# pulse.net
KiCad netlist of a schematic drawn in EAGLE
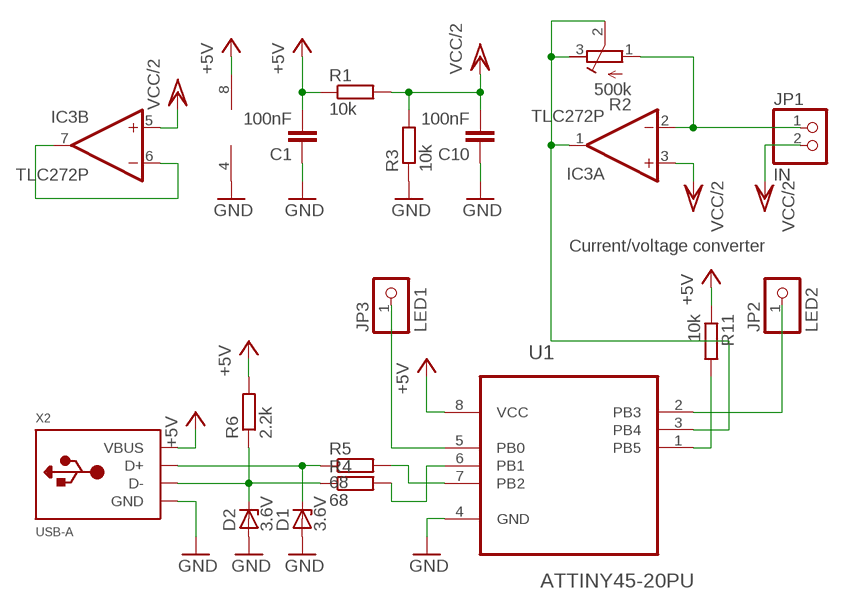
[diagram p0: schematic, sheet 1]

(export (version "E")
  (design (tool "Eeschema 10.0.6"))
  (components
    (comp (ref "C1")
      (value "100nF")
      (footprint "eagle-import:C075-032X103")
      (libsource (lib "eagle-import") (part "C-EU075-032X103"))
    )
    (comp (ref "C10")
      (value "100nF")
      (footprint "eagle-import:C050-025X075")
      (libsource (lib "eagle-import") (part "C-EU050-025X075"))
    )
    (comp (ref "D1")
      (value "3.6V")
      (footprint "eagle-import:ZDIO-2.5")
      (libsource (lib "eagle-import") (part "ZENER-DIODEZD-2.5"))
    )
    (comp (ref "D2")
      (value "3.6V")
      (footprint "eagle-import:ZDIO-5")
      (libsource (lib "eagle-import") (part "ZENER-DIODEZD-5"))
    )
    (comp (ref "IC3")
      (value "TLC272P")
      (footprint "eagle-import:DIL08")
      (libsource (lib "eagle-import") (part "TLC272P"))
    )
    (comp (ref "JP1")
      (value "IN")
      (footprint "eagle-import:1X02")
      (libsource (lib "eagle-import") (part "PINHD-1X2"))
    )
    (comp (ref "JP2")
      (value "LED2")
      (footprint "eagle-import:1X01")
      (libsource (lib "eagle-import") (part "PINHD-1X1"))
    )
    (comp (ref "JP3")
      (value "LED1")
      (footprint "eagle-import:1X01")
      (libsource (lib "eagle-import") (part "PINHD-1X1"))
    )
    (comp (ref "R1")
      (value "10k")
      (footprint "eagle-import:0207_12")
      (libsource (lib "eagle-import") (part "R-EU_0207/12"))
    )
    (comp (ref "R2")
      (value "500k")
      (footprint "eagle-import:RTRIM64W")
      (libsource (lib "eagle-import") (part "R-TRIMM64W"))
    )
    (comp (ref "R3")
      (value "10k")
      (footprint "eagle-import:0204V")
      (libsource (lib "eagle-import") (part "R-EU_0204/2V"))
    )
    (comp (ref "R4")
      (value "68")
      (footprint "eagle-import:0204V")
      (libsource (lib "eagle-import") (part "R-EU_0204/2V"))
    )
    (comp (ref "R5")
      (value "68")
      (footprint "eagle-import:0204V")
      (libsource (lib "eagle-import") (part "R-EU_0204/2V"))
    )
    (comp (ref "R6")
      (value "2.2k")
      (footprint "eagle-import:0204V")
      (libsource (lib "eagle-import") (part "R-EU_0204/2V"))
    )
    (comp (ref "R11")
      (value "10k")
      (footprint "eagle-import:0204_7")
      (libsource (lib "eagle-import") (part "R-EU_0204/7"))
    )
    (comp (ref "U1")
      (value "ATTINY45-20PU")
      (footprint "eagle-import:DIP254P762X533-8")
      (libsource (lib "eagle-import") (part "ATTINY45-20PU"))
    )
    (comp (ref "X2")
      (value "USB-A")
      (footprint "eagle-import:MOLEX_480371000")
      (libsource (lib "eagle-import") (part "USB-A"))
    )
  )
  (nets
    (net (code "1") (name "+5V") (class "Default")
      (node (ref "C1") (pin "2") (pinfunction "2_2") (pintype "passive"))
      (node (ref "IC3") (pin "8") (pinfunction "V+_8") (pintype "power_in"))
      (node (ref "R1") (pin "1") (pinfunction "1_1") (pintype "passive"))
      (node (ref "R11") (pin "1") (pinfunction "1_1") (pintype "passive"))
      (node (ref "R6") (pin "2") (pinfunction "2_2") (pintype "passive"))
      (node (ref "U1") (pin "8") (pinfunction "VCC_8") (pintype "power_in"))
      (node (ref "X2") (pin "1") (pinfunction "VBUS_1") (pintype "power_in"))
    )
    (net (code "2") (name "GND") (class "Default")
      (node (ref "C1") (pin "1") (pinfunction "1_1") (pintype "passive"))
      (node (ref "C10") (pin "1") (pinfunction "1_1") (pintype "passive"))
      (node (ref "D1") (pin "A") (pinfunction "A_A") (pintype "passive"))
      (node (ref "D2") (pin "A") (pinfunction "A_A") (pintype "passive"))
      (node (ref "IC3") (pin "4") (pinfunction "V-_4") (pintype "power_in"))
      (node (ref "R3") (pin "1") (pinfunction "1_1") (pintype "passive"))
      (node (ref "U1") (pin "4") (pinfunction "GND_4") (pintype "passive"))
      (node (ref "X2") (pin "4") (pinfunction "GND_4") (pintype "power_in"))
    )
    (net (code "3") (name "Net-(IC3A--IN)") (class "Default")
      (node (ref "IC3") (pin "2") (pinfunction "-IN_2") (pintype "input"))
      (node (ref "JP1") (pin "1") (pinfunction "1_1") (pintype "passive"))
      (node (ref "R2") (pin "1") (pinfunction "A_1") (pintype "passive"))
    )
    (net (code "4") (name "Net-(IC3A-OUT)") (class "Default")
      (node (ref "IC3") (pin "1") (pinfunction "OUT_1") (pintype "output"))
      (node (ref "R2") (pin "2") (pinfunction "S_2") (pintype "passive"))
      (node (ref "R2") (pin "3") (pinfunction "E_3") (pintype "passive"))
      (node (ref "U1") (pin "3") (pinfunction "PB4_3") (pintype "bidirectional"))
    )
    (net (code "5") (name "Net-(IC3B--IN)") (class "Default")
      (node (ref "IC3") (pin "6") (pinfunction "-IN_6") (pintype "input"))
      (node (ref "IC3") (pin "7") (pinfunction "OUT_7") (pintype "output"))
    )
    (net (code "6") (name "Net-(U1-PB0)") (class "Default")
      (node (ref "JP3") (pin "1") (pinfunction "1_1") (pintype "passive"))
      (node (ref "U1") (pin "5") (pinfunction "PB0_5") (pintype "bidirectional"))
    )
    (net (code "7") (name "Net-(U1-PB1)") (class "Default")
      (node (ref "R4") (pin "2") (pinfunction "2_2") (pintype "passive"))
      (node (ref "U1") (pin "6") (pinfunction "PB1_6") (pintype "bidirectional"))
    )
    (net (code "8") (name "Net-(U1-PB2)") (class "Default")
      (node (ref "R5") (pin "2") (pinfunction "2_2") (pintype "passive"))
      (node (ref "U1") (pin "7") (pinfunction "PB2_7") (pintype "bidirectional"))
    )
    (net (code "9") (name "Net-(U1-PB3)") (class "Default")
      (node (ref "JP2") (pin "1") (pinfunction "1_1") (pintype "passive"))
      (node (ref "U1") (pin "2") (pinfunction "PB3_2") (pintype "bidirectional"))
    )
    (net (code "10") (name "Net-(U1-PB5)") (class "Default")
      (node (ref "R11") (pin "2") (pinfunction "2_2") (pintype "passive"))
      (node (ref "U1") (pin "1") (pinfunction "PB5_1") (pintype "bidirectional"))
    )
    (net (code "11") (name "Net-(X2-D+)") (class "Default")
      (node (ref "D1") (pin "C") (pinfunction "C_C") (pintype "passive"))
      (node (ref "R5") (pin "1") (pinfunction "1_1") (pintype "passive"))
      (node (ref "X2") (pin "3") (pinfunction "D+_3") (pintype "bidirectional"))
    )
    (net (code "12") (name "Net-(X2-D-)") (class "Default")
      (node (ref "D2") (pin "C") (pinfunction "C_C") (pintype "passive"))
      (node (ref "R4") (pin "1") (pinfunction "1_1") (pintype "passive"))
      (node (ref "R6") (pin "1") (pinfunction "1_1") (pintype "passive"))
      (node (ref "X2") (pin "2") (pinfunction "D-_2") (pintype "bidirectional"))
    )
    (net (code "13") (name "VCC{slash}2") (class "Default")
      (node (ref "C10") (pin "2") (pinfunction "2_2") (pintype "passive"))
      (node (ref "IC3") (pin "3") (pinfunction "+IN_3") (pintype "input"))
      (node (ref "IC3") (pin "5") (pinfunction "+IN_5") (pintype "input"))
      (node (ref "JP1") (pin "2") (pinfunction "2_2") (pintype "passive"))
      (node (ref "R1") (pin "2") (pinfunction "2_2") (pintype "passive"))
      (node (ref "R3") (pin "2") (pinfunction "2_2") (pintype "passive"))
    )
  )
)
